# FubarStep_v12.net
KiCad netlist of a schematic drawn in EAGLE
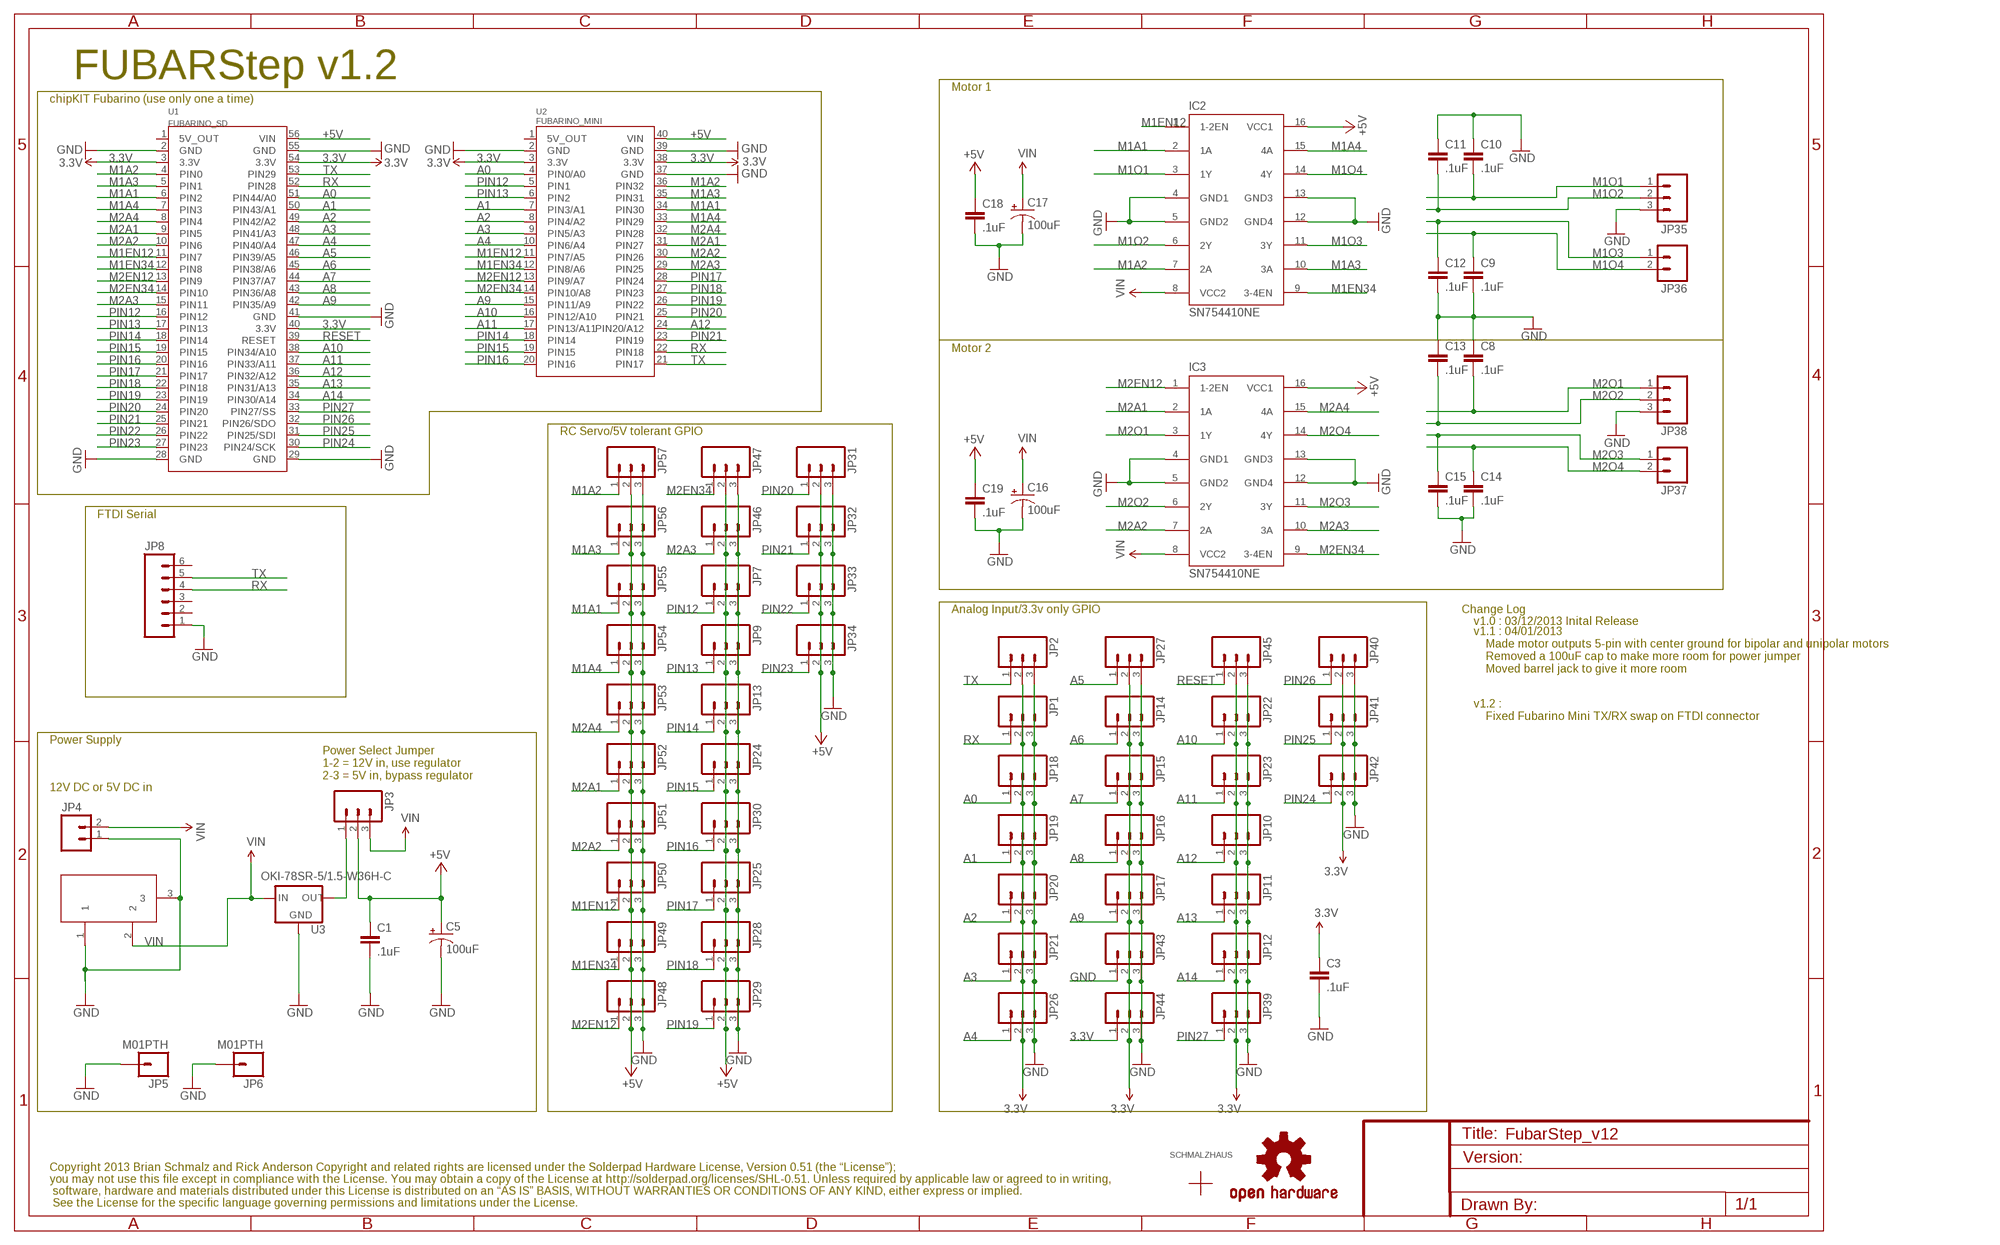
[diagram p0: schematic, sheet 1]

(export (version "E")
  (design (tool "Eeschema 10.0.6"))
  (components
    (comp (ref "C1")
      (value ".1uF")
      (footprint "eagle-import:CAP-PTH-SMALL")
      (libsource (lib "eagle-import") (part "CAPPTH"))
    )
    (comp (ref "C3")
      (value ".1uF")
      (footprint "eagle-import:CAP-PTH-SMALL")
      (libsource (lib "eagle-import") (part "CAPPTH"))
    )
    (comp (ref "C5")
      (value "100uF")
      (footprint "eagle-import:CPOL-RADIAL-100UF-25V")
      (libsource (lib "eagle-import") (part "CAP_POLPTH1"))
    )
    (comp (ref "C8")
      (value ".1uF")
      (footprint "eagle-import:CAP-PTH-SMALL")
      (libsource (lib "eagle-import") (part "CAPPTH"))
    )
    (comp (ref "C9")
      (value ".1uF")
      (footprint "eagle-import:CAP-PTH-SMALL")
      (libsource (lib "eagle-import") (part "CAPPTH"))
    )
    (comp (ref "C10")
      (value ".1uF")
      (footprint "eagle-import:CAP-PTH-SMALL")
      (libsource (lib "eagle-import") (part "CAPPTH"))
    )
    (comp (ref "C11")
      (value ".1uF")
      (footprint "eagle-import:CAP-PTH-SMALL")
      (libsource (lib "eagle-import") (part "CAPPTH"))
    )
    (comp (ref "C12")
      (value ".1uF")
      (footprint "eagle-import:CAP-PTH-SMALL")
      (libsource (lib "eagle-import") (part "CAPPTH"))
    )
    (comp (ref "C13")
      (value ".1uF")
      (footprint "eagle-import:CAP-PTH-SMALL")
      (libsource (lib "eagle-import") (part "CAPPTH"))
    )
    (comp (ref "C14")
      (value ".1uF")
      (footprint "eagle-import:CAP-PTH-SMALL")
      (libsource (lib "eagle-import") (part "CAPPTH"))
    )
    (comp (ref "C15")
      (value ".1uF")
      (footprint "eagle-import:CAP-PTH-SMALL")
      (libsource (lib "eagle-import") (part "CAPPTH"))
    )
    (comp (ref "C16")
      (value "100uF")
      (footprint "eagle-import:CPOL-RADIAL-100UF-25V")
      (libsource (lib "eagle-import") (part "CAP_POLPTH1"))
    )
    (comp (ref "C17")
      (value "100uF")
      (footprint "eagle-import:CPOL-RADIAL-100UF-25V")
      (libsource (lib "eagle-import") (part "CAP_POLPTH1"))
    )
    (comp (ref "C18")
      (value ".1uF")
      (footprint "eagle-import:CAP-PTH-SMALL")
      (libsource (lib "eagle-import") (part "CAPPTH"))
    )
    (comp (ref "C19")
      (value ".1uF")
      (footprint "eagle-import:CAP-PTH-SMALL")
      (libsource (lib "eagle-import") (part "CAPPTH"))
    )
    (comp (ref "IC2")
      (value "SN754410NE")
      (footprint "eagle-import:DIL16")
      (fields (field (name "MF") "Arrow Electronics") (field (name "MPN") "L293E"))
      (libsource (lib "eagle-import") (part "L293E"))
    )
    (comp (ref "IC3")
      (value "SN754410NE")
      (footprint "eagle-import:DIL16")
      (fields (field (name "MF") "Arrow Electronics") (field (name "MPN") "L293E"))
      (libsource (lib "eagle-import") (part "L293E"))
    )
    (comp (ref "JP1")
      (value "M03PTH")
      (footprint "eagle-import:1X03")
      (libsource (lib "eagle-import") (part "M03PTH"))
    )
    (comp (ref "JP2")
      (value "M03PTH")
      (footprint "eagle-import:1X03")
      (libsource (lib "eagle-import") (part "M03PTH"))
    )
    (comp (ref "JP3")
      (value "M03PTH")
      (footprint "eagle-import:1X03")
      (libsource (lib "eagle-import") (part "M03PTH"))
    )
    (comp (ref "JP4")
      (value "M023.5MM")
      (footprint "eagle-import:SCREWTERMINAL-3.5MM-2")
      (libsource (lib "eagle-import") (part "M023.5MM"))
    )
    (comp (ref "JP5")
      (value "M01PTH")
      (footprint "eagle-import:1X01")
      (libsource (lib "eagle-import") (part "M01PTH"))
    )
    (comp (ref "JP6")
      (value "M01PTH")
      (footprint "eagle-import:1X01")
      (libsource (lib "eagle-import") (part "M01PTH"))
    )
    (comp (ref "JP7")
      (value "M03PTH")
      (footprint "eagle-import:1X03")
      (libsource (lib "eagle-import") (part "M03PTH"))
    )
    (comp (ref "JP8")
      (value "M06LOCK")
      (footprint "eagle-import:1X06_LOCK")
      (libsource (lib "eagle-import") (part "M06LOCK"))
    )
    (comp (ref "JP9")
      (value "M03PTH")
      (footprint "eagle-import:1X03")
      (libsource (lib "eagle-import") (part "M03PTH"))
    )
    (comp (ref "JP10")
      (value "M03PTH")
      (footprint "eagle-import:1X03")
      (libsource (lib "eagle-import") (part "M03PTH"))
    )
    (comp (ref "JP11")
      (value "M03PTH")
      (footprint "eagle-import:1X03")
      (libsource (lib "eagle-import") (part "M03PTH"))
    )
    (comp (ref "JP12")
      (value "M03PTH")
      (footprint "eagle-import:1X03")
      (libsource (lib "eagle-import") (part "M03PTH"))
    )
    (comp (ref "JP13")
      (value "M03PTH")
      (footprint "eagle-import:1X03")
      (libsource (lib "eagle-import") (part "M03PTH"))
    )
    (comp (ref "JP14")
      (value "M03PTH")
      (footprint "eagle-import:1X03")
      (libsource (lib "eagle-import") (part "M03PTH"))
    )
    (comp (ref "JP15")
      (value "M03PTH")
      (footprint "eagle-import:1X03")
      (libsource (lib "eagle-import") (part "M03PTH"))
    )
    (comp (ref "JP16")
      (value "M03PTH")
      (footprint "eagle-import:1X03")
      (libsource (lib "eagle-import") (part "M03PTH"))
    )
    (comp (ref "JP17")
      (value "M03PTH")
      (footprint "eagle-import:1X03")
      (libsource (lib "eagle-import") (part "M03PTH"))
    )
    (comp (ref "JP18")
      (value "M03PTH")
      (footprint "eagle-import:1X03")
      (libsource (lib "eagle-import") (part "M03PTH"))
    )
    (comp (ref "JP19")
      (value "M03PTH")
      (footprint "eagle-import:1X03")
      (libsource (lib "eagle-import") (part "M03PTH"))
    )
    (comp (ref "JP20")
      (value "M03PTH")
      (footprint "eagle-import:1X03")
      (libsource (lib "eagle-import") (part "M03PTH"))
    )
    (comp (ref "JP21")
      (value "M03PTH")
      (footprint "eagle-import:1X03")
      (libsource (lib "eagle-import") (part "M03PTH"))
    )
    (comp (ref "JP22")
      (value "M03PTH")
      (footprint "eagle-import:1X03")
      (libsource (lib "eagle-import") (part "M03PTH"))
    )
    (comp (ref "JP23")
      (value "M03PTH")
      (footprint "eagle-import:1X03")
      (libsource (lib "eagle-import") (part "M03PTH"))
    )
    (comp (ref "JP24")
      (value "M03PTH")
      (footprint "eagle-import:1X03")
      (libsource (lib "eagle-import") (part "M03PTH"))
    )
    (comp (ref "JP25")
      (value "M03PTH")
      (footprint "eagle-import:1X03")
      (libsource (lib "eagle-import") (part "M03PTH"))
    )
    (comp (ref "JP26")
      (value "M03PTH")
      (footprint "eagle-import:1X03")
      (libsource (lib "eagle-import") (part "M03PTH"))
    )
    (comp (ref "JP27")
      (value "M03PTH")
      (footprint "eagle-import:1X03")
      (libsource (lib "eagle-import") (part "M03PTH"))
    )
    (comp (ref "JP28")
      (value "M03PTH")
      (footprint "eagle-import:1X03")
      (libsource (lib "eagle-import") (part "M03PTH"))
    )
    (comp (ref "JP29")
      (value "M03PTH")
      (footprint "eagle-import:1X03")
      (libsource (lib "eagle-import") (part "M03PTH"))
    )
    (comp (ref "JP30")
      (value "M03PTH")
      (footprint "eagle-import:1X03")
      (libsource (lib "eagle-import") (part "M03PTH"))
    )
    (comp (ref "JP31")
      (value "M03PTH")
      (footprint "eagle-import:1X03")
      (libsource (lib "eagle-import") (part "M03PTH"))
    )
    (comp (ref "JP32")
      (value "M03PTH")
      (footprint "eagle-import:1X03")
      (libsource (lib "eagle-import") (part "M03PTH"))
    )
    (comp (ref "JP33")
      (value "M03PTH")
      (footprint "eagle-import:1X03")
      (libsource (lib "eagle-import") (part "M03PTH"))
    )
    (comp (ref "JP34")
      (value "M03PTH")
      (footprint "eagle-import:1X03")
      (libsource (lib "eagle-import") (part "M03PTH"))
    )
    (comp (ref "JP35")
      (value "M03SCREW")
      (footprint "eagle-import:SCREWTERMINAL-3.5MM-3")
      (libsource (lib "eagle-import") (part "M03SCREW"))
    )
    (comp (ref "JP36")
      (value "M023.5MM")
      (footprint "eagle-import:SCREWTERMINAL-3.5MM-2")
      (libsource (lib "eagle-import") (part "M023.5MM"))
    )
    (comp (ref "JP37")
      (value "M023.5MM")
      (footprint "eagle-import:SCREWTERMINAL-3.5MM-2")
      (libsource (lib "eagle-import") (part "M023.5MM"))
    )
    (comp (ref "JP38")
      (value "M03SCREW")
      (footprint "eagle-import:SCREWTERMINAL-3.5MM-3")
      (libsource (lib "eagle-import") (part "M03SCREW"))
    )
    (comp (ref "JP39")
      (value "M03PTH")
      (footprint "eagle-import:1X03")
      (libsource (lib "eagle-import") (part "M03PTH"))
    )
    (comp (ref "JP40")
      (value "M03PTH")
      (footprint "eagle-import:1X03")
      (libsource (lib "eagle-import") (part "M03PTH"))
    )
    (comp (ref "JP41")
      (value "M03PTH")
      (footprint "eagle-import:1X03")
      (libsource (lib "eagle-import") (part "M03PTH"))
    )
    (comp (ref "JP42")
      (value "M03PTH")
      (footprint "eagle-import:1X03")
      (libsource (lib "eagle-import") (part "M03PTH"))
    )
    (comp (ref "JP43")
      (value "M03PTH")
      (footprint "eagle-import:1X03")
      (libsource (lib "eagle-import") (part "M03PTH"))
    )
    (comp (ref "JP44")
      (value "M03PTH")
      (footprint "eagle-import:1X03")
      (libsource (lib "eagle-import") (part "M03PTH"))
    )
    (comp (ref "JP45")
      (value "M03PTH")
      (footprint "eagle-import:1X03")
      (libsource (lib "eagle-import") (part "M03PTH"))
    )
    (comp (ref "JP46")
      (value "M03PTH")
      (footprint "eagle-import:1X03")
      (libsource (lib "eagle-import") (part "M03PTH"))
    )
    (comp (ref "JP47")
      (value "M03PTH")
      (footprint "eagle-import:1X03")
      (libsource (lib "eagle-import") (part "M03PTH"))
    )
    (comp (ref "JP48")
      (value "M03PTH")
      (footprint "eagle-import:1X03")
      (libsource (lib "eagle-import") (part "M03PTH"))
    )
    (comp (ref "JP49")
      (value "M03PTH")
      (footprint "eagle-import:1X03")
      (libsource (lib "eagle-import") (part "M03PTH"))
    )
    (comp (ref "JP50")
      (value "M03PTH")
      (footprint "eagle-import:1X03")
      (libsource (lib "eagle-import") (part "M03PTH"))
    )
    (comp (ref "JP51")
      (value "M03PTH")
      (footprint "eagle-import:1X03")
      (libsource (lib "eagle-import") (part "M03PTH"))
    )
    (comp (ref "JP52")
      (value "M03PTH")
      (footprint "eagle-import:1X03")
      (libsource (lib "eagle-import") (part "M03PTH"))
    )
    (comp (ref "JP53")
      (value "M03PTH")
      (footprint "eagle-import:1X03")
      (libsource (lib "eagle-import") (part "M03PTH"))
    )
    (comp (ref "JP54")
      (value "M03PTH")
      (footprint "eagle-import:1X03")
      (libsource (lib "eagle-import") (part "M03PTH"))
    )
    (comp (ref "JP55")
      (value "M03PTH")
      (footprint "eagle-import:1X03")
      (libsource (lib "eagle-import") (part "M03PTH"))
    )
    (comp (ref "JP56")
      (value "M03PTH")
      (footprint "eagle-import:1X03")
      (libsource (lib "eagle-import") (part "M03PTH"))
    )
    (comp (ref "JP57")
      (value "M03PTH")
      (footprint "eagle-import:1X03")
      (libsource (lib "eagle-import") (part "M03PTH"))
    )
    (comp (ref "LOGO1")
      (value "OSHW-LOGOM")
      (footprint "eagle-import:OSHW-LOGO-M")
      (libsource (lib "eagle-import") (part "OSHW-LOGOM"))
    )
    (comp (ref "U$1")
      (value "SCHMALZHAUSSCHMALZHAUS_SMALL")
      (footprint "eagle-import:SCHMALZHAUS_SMALL")
      (libsource (lib "eagle-import") (part "SCHMALZHAUSSCHMALZHAUS_SMALL"))
    )
    (comp (ref "U1")
      (value "FUBARINO_SD")
      (footprint "eagle-import:FUBARINO_SD")
      (libsource (lib "eagle-import") (part "FUBARINO_SD"))
    )
    (comp (ref "U2")
      (value "FUBARINO_MINI")
      (footprint "eagle-import:FUBARINO_MINI")
      (libsource (lib "eagle-import") (part "FUBARINO_MINI"))
    )
    (comp (ref "U3")
      (value "OKI-78SR-5/1.5-W36H-C")
      (footprint "eagle-import:TO220-IGO")
      (libsource (lib "eagle-import") (part "V_REG_78XXSINK"))
    )
    (comp (ref "X1")
      (value "DC21MMX")
      (footprint "eagle-import:DC-21MM")
      (libsource (lib "eagle-import") (part "DC21MMX"))
    )
  )
  (nets
    (net (code "1") (name "+5V") (class "Default")
      (node (ref "C1") (pin "1") (pinfunction "1_1") (pintype "passive"))
      (node (ref "C18") (pin "1") (pinfunction "1_1") (pintype "passive"))
      (node (ref "C19") (pin "1") (pinfunction "1_1") (pintype "passive"))
      (node (ref "C5") (pin "1") (pinfunction "+_1") (pintype "passive"))
      (node (ref "IC2") (pin "16") (pinfunction "VCC1_16") (pintype "power_in"))
      (node (ref "IC3") (pin "16") (pinfunction "VCC1_16") (pintype "power_in"))
      (node (ref "JP13") (pin "2") (pinfunction "2_2") (pintype "passive"))
      (node (ref "JP24") (pin "2") (pinfunction "2_2") (pintype "passive"))
      (node (ref "JP25") (pin "2") (pinfunction "2_2") (pintype "passive"))
      (node (ref "JP28") (pin "2") (pinfunction "2_2") (pintype "passive"))
      (node (ref "JP29") (pin "2") (pinfunction "2_2") (pintype "passive"))
      (node (ref "JP3") (pin "2") (pinfunction "2_2") (pintype "passive"))
      (node (ref "JP30") (pin "2") (pinfunction "2_2") (pintype "passive"))
      (node (ref "JP31") (pin "2") (pinfunction "2_2") (pintype "passive"))
      (node (ref "JP32") (pin "2") (pinfunction "2_2") (pintype "passive"))
      (node (ref "JP33") (pin "2") (pinfunction "2_2") (pintype "passive"))
      (node (ref "JP34") (pin "2") (pinfunction "2_2") (pintype "passive"))
      (node (ref "JP46") (pin "2") (pinfunction "2_2") (pintype "passive"))
      (node (ref "JP47") (pin "2") (pinfunction "2_2") (pintype "passive"))
      (node (ref "JP48") (pin "2") (pinfunction "2_2") (pintype "passive"))
      (node (ref "JP49") (pin "2") (pinfunction "2_2") (pintype "passive"))
      (node (ref "JP50") (pin "2") (pinfunction "2_2") (pintype "passive"))
      (node (ref "JP51") (pin "2") (pinfunction "2_2") (pintype "passive"))
      (node (ref "JP52") (pin "2") (pinfunction "2_2") (pintype "passive"))
      (node (ref "JP53") (pin "2") (pinfunction "2_2") (pintype "passive"))
      (node (ref "JP54") (pin "2") (pinfunction "2_2") (pintype "passive"))
      (node (ref "JP55") (pin "2") (pinfunction "2_2") (pintype "passive"))
      (node (ref "JP56") (pin "2") (pinfunction "2_2") (pintype "passive"))
      (node (ref "JP57") (pin "2") (pinfunction "2_2") (pintype "passive"))
      (node (ref "JP7") (pin "2") (pinfunction "2_2") (pintype "passive"))
      (node (ref "JP9") (pin "2") (pinfunction "2_2") (pintype "passive"))
      (node (ref "U1") (pin "56") (pinfunction "VIN_56") (pintype "bidirectional"))
      (node (ref "U2") (pin "40") (pinfunction "VIN_40") (pintype "bidirectional"))
    )
    (net (code "2") (name "/A0") (class "Default")
      (node (ref "JP18") (pin "1") (pinfunction "1_1") (pintype "passive"))
      (node (ref "U1") (pin "51") (pinfunction "PIN44/A0_51") (pintype "bidirectional"))
      (node (ref "U2") (pin "4") (pinfunction "PIN0/A0_4") (pintype "bidirectional"))
    )
    (net (code "3") (name "/A1") (class "Default")
      (node (ref "JP19") (pin "1") (pinfunction "1_1") (pintype "passive"))
      (node (ref "U1") (pin "50") (pinfunction "PIN43/A1_50") (pintype "bidirectional"))
      (node (ref "U2") (pin "7") (pinfunction "PIN3/A1_7") (pintype "bidirectional"))
    )
    (net (code "4") (name "/A2") (class "Default")
      (node (ref "JP20") (pin "1") (pinfunction "1_1") (pintype "passive"))
      (node (ref "U1") (pin "49") (pinfunction "PIN42/A2_49") (pintype "bidirectional"))
      (node (ref "U2") (pin "8") (pinfunction "PIN4/A2_8") (pintype "bidirectional"))
    )
    (net (code "5") (name "/A3") (class "Default")
      (node (ref "JP21") (pin "1") (pinfunction "1_1") (pintype "passive"))
      (node (ref "U1") (pin "48") (pinfunction "PIN41/A3_48") (pintype "bidirectional"))
      (node (ref "U2") (pin "9") (pinfunction "PIN5/A3_9") (pintype "bidirectional"))
    )
    (net (code "6") (name "/A4") (class "Default")
      (node (ref "JP26") (pin "1") (pinfunction "1_1") (pintype "passive"))
      (node (ref "U1") (pin "47") (pinfunction "PIN40/A4_47") (pintype "bidirectional"))
      (node (ref "U2") (pin "10") (pinfunction "PIN6/A4_10") (pintype "bidirectional"))
    )
    (net (code "7") (name "/A5") (class "Default")
      (node (ref "JP27") (pin "1") (pinfunction "1_1") (pintype "passive"))
      (node (ref "U1") (pin "46") (pinfunction "PIN39/A5_46") (pintype "bidirectional"))
    )
    (net (code "8") (name "/A6") (class "Default")
      (node (ref "JP14") (pin "1") (pinfunction "1_1") (pintype "passive"))
      (node (ref "U1") (pin "45") (pinfunction "PIN38/A6_45") (pintype "bidirectional"))
    )
    (net (code "9") (name "/A7") (class "Default")
      (node (ref "JP15") (pin "1") (pinfunction "1_1") (pintype "passive"))
      (node (ref "U1") (pin "44") (pinfunction "PIN37/A7_44") (pintype "bidirectional"))
    )
    (net (code "10") (name "/A8") (class "Default")
      (node (ref "JP16") (pin "1") (pinfunction "1_1") (pintype "passive"))
      (node (ref "U1") (pin "43") (pinfunction "PIN36/A8_43") (pintype "bidirectional"))
    )
    (net (code "11") (name "/A9") (class "Default")
      (node (ref "JP17") (pin "1") (pinfunction "1_1") (pintype "passive"))
      (node (ref "U1") (pin "42") (pinfunction "PIN35/A9_42") (pintype "bidirectional"))
      (node (ref "U2") (pin "15") (pinfunction "PIN11/A9_15") (pintype "bidirectional"))
    )
    (net (code "12") (name "/A10") (class "Default")
      (node (ref "JP22") (pin "1") (pinfunction "1_1") (pintype "passive"))
      (node (ref "U1") (pin "38") (pinfunction "PIN34/A10_38") (pintype "bidirectional"))
      (node (ref "U2") (pin "16") (pinfunction "PIN12/A10_16") (pintype "bidirectional"))
    )
    (net (code "13") (name "/A11") (class "Default")
      (node (ref "JP23") (pin "1") (pinfunction "1_1") (pintype "passive"))
      (node (ref "U1") (pin "37") (pinfunction "PIN33/A11_37") (pintype "bidirectional"))
      (node (ref "U2") (pin "17") (pinfunction "PIN13/A11_17") (pintype "bidirectional"))
    )
    (net (code "14") (name "/A12") (class "Default")
      (node (ref "JP10") (pin "1") (pinfunction "1_1") (pintype "passive"))
      (node (ref "U1") (pin "36") (pinfunction "PIN32/A12_36") (pintype "bidirectional"))
      (node (ref "U2") (pin "24") (pinfunction "PIN20/A12_24") (pintype "bidirectional"))
    )
    (net (code "15") (name "/A13") (class "Default")
      (node (ref "JP11") (pin "1") (pinfunction "1_1") (pintype "passive"))
      (node (ref "U1") (pin "35") (pinfunction "PIN31/A13_35") (pintype "bidirectional"))
    )
    (net (code "16") (name "/A14") (class "Default")
      (node (ref "JP12") (pin "1") (pinfunction "1_1") (pintype "passive"))
      (node (ref "U1") (pin "34") (pinfunction "PIN30/A14_34") (pintype "bidirectional"))
    )
    (net (code "17") (name "/M1A1") (class "Default")
      (node (ref "IC2") (pin "2") (pinfunction "1A_2") (pintype "input"))
      (node (ref "JP55") (pin "1") (pinfunction "1_1") (pintype "passive"))
      (node (ref "U1") (pin "6") (pinfunction "PIN2_6") (pintype "bidirectional"))
      (node (ref "U2") (pin "34") (pinfunction "PIN30_34") (pintype "bidirectional"))
    )
    (net (code "18") (name "/M1A2") (class "Default")
      (node (ref "IC2") (pin "7") (pinfunction "2A_7") (pintype "input"))
      (node (ref "JP57") (pin "1") (pinfunction "1_1") (pintype "passive"))
      (node (ref "U1") (pin "4") (pinfunction "PIN0_4") (pintype "bidirectional"))
      (node (ref "U2") (pin "36") (pinfunction "PIN32_36") (pintype "bidirectional"))
    )
    (net (code "19") (name "/M1A3") (class "Default")
      (node (ref "IC2") (pin "10") (pinfunction "3A_10") (pintype "input"))
      (node (ref "JP56") (pin "1") (pinfunction "1_1") (pintype "passive"))
      (node (ref "U1") (pin "5") (pinfunction "PIN1_5") (pintype "bidirectional"))
      (node (ref "U2") (pin "35") (pinfunction "PIN31_35") (pintype "bidirectional"))
    )
    (net (code "20") (name "/M1A4") (class "Default")
      (node (ref "IC2") (pin "15") (pinfunction "4A_15") (pintype "input"))
      (node (ref "JP54") (pin "1") (pinfunction "1_1") (pintype "passive"))
      (node (ref "U1") (pin "7") (pinfunction "PIN3_7") (pintype "bidirectional"))
      (node (ref "U2") (pin "33") (pinfunction "PIN29_33") (pintype "bidirectional"))
    )
    (net (code "21") (name "/M1EN12") (class "Default")
      (node (ref "IC2") (pin "1") (pinfunction "1-2EN_1") (pintype "input"))
      (node (ref "JP50") (pin "1") (pinfunction "1_1") (pintype "passive"))
      (node (ref "U1") (pin "11") (pinfunction "PIN7_11") (pintype "bidirectional"))
      (node (ref "U2") (pin "11") (pinfunction "PIN7/A5_11") (pintype "bidirectional"))
    )
    (net (code "22") (name "/M1EN34") (class "Default")
      (node (ref "IC2") (pin "9") (pinfunction "3-4EN_9") (pintype "input"))
      (node (ref "JP49") (pin "1") (pinfunction "1_1") (pintype "passive"))
      (node (ref "U1") (pin "12") (pinfunction "PIN8_12") (pintype "bidirectional"))
      (node (ref "U2") (pin "12") (pinfunction "PIN8/A6_12") (pintype "bidirectional"))
    )
    (net (code "23") (name "/M1O1") (class "Default")
      (node (ref "C10") (pin "2") (pinfunction "2_2") (pintype "passive"))
      (node (ref "IC2") (pin "3") (pinfunction "1Y_3") (pintype "output"))
      (node (ref "JP35") (pin "1") (pinfunction "1_1") (pintype "passive"))
    )
    (net (code "24") (name "/M1O2") (class "Default")
      (node (ref "C11") (pin "2") (pinfunction "2_2") (pintype "passive"))
      (node (ref "IC2") (pin "6") (pinfunction "2Y_6") (pintype "output"))
      (node (ref "JP35") (pin "2") (pinfunction "2_2") (pintype "passive"))
    )
    (net (code "25") (name "/M1O3") (class "Default")
      (node (ref "C12") (pin "1") (pinfunction "1_1") (pintype "passive"))
      (node (ref "IC2") (pin "11") (pinfunction "3Y_11") (pintype "output"))
      (node (ref "JP36") (pin "1") (pinfunction "1_1") (pintype "passive"))
    )
    (net (code "26") (name "/M1O4") (class "Default")
      (node (ref "C9") (pin "1") (pinfunction "1_1") (pintype "passive"))
      (node (ref "IC2") (pin "14") (pinfunction "4Y_14") (pintype "output"))
      (node (ref "JP36") (pin "2") (pinfunction "2_2") (pintype "passive"))
    )
    (net (code "27") (name "/M2A1") (class "Default")
      (node (ref "IC3") (pin "2") (pinfunction "1A_2") (pintype "input"))
      (node (ref "JP52") (pin "1") (pinfunction "1_1") (pintype "passive"))
      (node (ref "U1") (pin "9") (pinfunction "PIN5_9") (pintype "bidirectional"))
      (node (ref "U2") (pin "31") (pinfunction "PIN27_31") (pintype "bidirectional"))
    )
    (net (code "28") (name "/M2A2") (class "Default")
      (node (ref "IC3") (pin "7") (pinfunction "2A_7") (pintype "input"))
      (node (ref "JP51") (pin "1") (pinfunction "1_1") (pintype "passive"))
      (node (ref "U1") (pin "10") (pinfunction "PIN6_10") (pintype "bidirectional"))
      (node (ref "U2") (pin "30") (pinfunction "PIN26_30") (pintype "bidirectional"))
    )
    (net (code "29") (name "/M2A3") (class "Default")
      (node (ref "IC3") (pin "10") (pinfunction "3A_10") (pintype "input"))
      (node (ref "JP46") (pin "1") (pinfunction "1_1") (pintype "passive"))
      (node (ref "U1") (pin "15") (pinfunction "PIN11_15") (pintype "bidirectional"))
      (node (ref "U2") (pin "29") (pinfunction "PIN25_29") (pintype "bidirectional"))
    )
    (net (code "30") (name "/M2A4") (class "Default")
      (node (ref "IC3") (pin "15") (pinfunction "4A_15") (pintype "input"))
      (node (ref "JP53") (pin "1") (pinfunction "1_1") (pintype "passive"))
      (node (ref "U1") (pin "8") (pinfunction "PIN4_8") (pintype "bidirectional"))
      (node (ref "U2") (pin "32") (pinfunction "PIN28_32") (pintype "bidirectional"))
    )
    (net (code "31") (name "/M2EN12") (class "Default")
      (node (ref "IC3") (pin "1") (pinfunction "1-2EN_1") (pintype "input"))
      (node (ref "JP48") (pin "1") (pinfunction "1_1") (pintype "passive"))
      (node (ref "U1") (pin "13") (pinfunction "PIN9_13") (pintype "bidirectional"))
      (node (ref "U2") (pin "13") (pinfunction "PIN9/A7_13") (pintype "bidirectional"))
    )
    (net (code "32") (name "/M2EN34") (class "Default")
      (node (ref "IC3") (pin "9") (pinfunction "3-4EN_9") (pintype "input"))
      (node (ref "JP47") (pin "1") (pinfunction "1_1") (pintype "passive"))
      (node (ref "U1") (pin "14") (pinfunction "PIN10_14") (pintype "bidirectional"))
      (node (ref "U2") (pin "14") (pinfunction "PIN10/A8_14") (pintype "bidirectional"))
    )
    (net (code "33") (name "/M2O1") (class "Default")
      (node (ref "C8") (pin "2") (pinfunction "2_2") (pintype "passive"))
      (node (ref "IC3") (pin "3") (pinfunction "1Y_3") (pintype "output"))
      (node (ref "JP38") (pin "1") (pinfunction "1_1") (pintype "passive"))
    )
    (net (code "34") (name "/M2O2") (class "Default")
      (node (ref "C13") (pin "2") (pinfunction "2_2") (pintype "passive"))
      (node (ref "IC3") (pin "6") (pinfunction "2Y_6") (pintype "output"))
      (node (ref "JP38") (pin "2") (pinfunction "2_2") (pintype "passive"))
    )
    (net (code "35") (name "/M2O3") (class "Default")
      (node (ref "C15") (pin "1") (pinfunction "1_1") (pintype "passive"))
      (node (ref "IC3") (pin "11") (pinfunction "3Y_11") (pintype "output"))
      (node (ref "JP37") (pin "1") (pinfunction "1_1") (pintype "passive"))
    )
    (net (code "36") (name "/M2O4") (class "Default")
      (node (ref "C14") (pin "1") (pinfunction "1_1") (pintype "passive"))
      (node (ref "IC3") (pin "14") (pinfunction "4Y_14") (pintype "output"))
      (node (ref "JP37") (pin "2") (pinfunction "2_2") (pintype "passive"))
    )
    (net (code "37") (name "/PIN12") (class "Default")
      (node (ref "JP7") (pin "1") (pinfunction "1_1") (pintype "passive"))
      (node (ref "U1") (pin "16") (pinfunction "PIN12_16") (pintype "bidirectional"))
      (node (ref "U2") (pin "5") (pinfunction "PIN1_5") (pintype "bidirectional"))
    )
    (net (code "38") (name "/PIN13") (class "Default")
      (node (ref "JP9") (pin "1") (pinfunction "1_1") (pintype "passive"))
      (node (ref "U1") (pin "17") (pinfunction "PIN13_17") (pintype "bidirectional"))
      (node (ref "U2") (pin "6") (pinfunction "PIN2_6") (pintype "bidirectional"))
    )
    (net (code "39") (name "/PIN14") (class "Default")
      (node (ref "JP13") (pin "1") (pinfunction "1_1") (pintype "passive"))
      (node (ref "U1") (pin "18") (pinfunction "PIN14_18") (pintype "bidirectional"))
      (node (ref "U2") (pin "18") (pinfunction "PIN14_18") (pintype "bidirectional"))
    )
    (net (code "40") (name "/PIN15") (class "Default")
      (node (ref "JP24") (pin "1") (pinfunction "1_1") (pintype "passive"))
      (node (ref "U1") (pin "19") (pinfunction "PIN15_19") (pintype "bidirectional"))
      (node (ref "U2") (pin "19") (pinfunction "PIN15_19") (pintype "bidirectional"))
    )
    (net (code "41") (name "/PIN16") (class "Default")
      (node (ref "JP30") (pin "1") (pinfunction "1_1") (pintype "passive"))
      (node (ref "U1") (pin "20") (pinfunction "PIN16_20") (pintype "bidirectional"))
      (node (ref "U2") (pin "20") (pinfunction "PIN16_20") (pintype "bidirectional"))
    )
    (net (code "42") (name "/PIN17") (class "Default")
      (node (ref "JP25") (pin "1") (pinfunction "1_1") (pintype "passive"))
      (node (ref "U1") (pin "21") (pinfunction "PIN17_21") (pintype "bidirectional"))
      (node (ref "U2") (pin "28") (pinfunction "PIN24_28") (pintype "bidirectional"))
    )
    (net (code "43") (name "/PIN18") (class "Default")
      (node (ref "JP28") (pin "1") (pinfunction "1_1") (pintype "passive"))
      (node (ref "U1") (pin "22") (pinfunction "PIN18_22") (pintype "bidirectional"))
      (node (ref "U2") (pin "27") (pinfunction "PIN23_27") (pintype "bidirectional"))
    )
    (net (code "44") (name "/PIN19") (class "Default")
      (node (ref "JP29") (pin "1") (pinfunction "1_1") (pintype "passive"))
      (node (ref "U1") (pin "23") (pinfunction "PIN19_23") (pintype "bidirectional"))
      (node (ref "U2") (pin "26") (pinfunction "PIN22_26") (pintype "bidirectional"))
    )
    (net (code "45") (name "/PIN20") (class "Default")
      (node (ref "JP31") (pin "1") (pinfunction "1_1") (pintype "passive"))
      (node (ref "U1") (pin "24") (pinfunction "PIN20_24") (pintype "bidirectional"))
      (node (ref "U2") (pin "25") (pinfunction "PIN21_25") (pintype "bidirectional"))
    )
    (net (code "46") (name "/PIN21") (class "Default")
      (node (ref "JP32") (pin "1") (pinfunction "1_1") (pintype "passive"))
      (node (ref "U1") (pin "25") (pinfunction "PIN21_25") (pintype "bidirectional"))
      (node (ref "U2") (pin "23") (pinfunction "PIN19_23") (pintype "bidirectional"))
    )
    (net (code "47") (name "/PIN22") (class "Default")
      (node (ref "JP33") (pin "1") (pinfunction "1_1") (pintype "passive"))
      (node (ref "U1") (pin "26") (pinfunction "PIN22_26") (pintype "bidirectional"))
    )
    (net (code "48") (name "/PIN23") (class "Default")
      (node (ref "JP34") (pin "1") (pinfunction "1_1") (pintype "passive"))
      (node (ref "U1") (pin "27") (pinfunction "PIN23_27") (pintype "bidirectional"))
    )
    (net (code "49") (name "/PIN24") (class "Default")
      (node (ref "JP42") (pin "1") (pinfunction "1_1") (pintype "passive"))
      (node (ref "U1") (pin "30") (pinfunction "PIN24/SCK_30") (pintype "bidirectional"))
    )
    (net (code "50") (name "/PIN25") (class "Default")
      (node (ref "JP41") (pin "1") (pinfunction "1_1") (pintype "passive"))
      (node (ref "U1") (pin "31") (pinfunction "PIN25/SDI_31") (pintype "bidirectional"))
    )
    (net (code "51") (name "/PIN26") (class "Default")
      (node (ref "JP40") (pin "1") (pinfunction "1_1") (pintype "passive"))
      (node (ref "U1") (pin "32") (pinfunction "PIN26/SDO_32") (pintype "bidirectional"))
    )
    (net (code "52") (name "/PIN27") (class "Default")
      (node (ref "JP39") (pin "1") (pinfunction "1_1") (pintype "passive"))
      (node (ref "U1") (pin "33") (pinfunction "PIN27/SS_33") (pintype "bidirectional"))
    )
    (net (code "53") (name "/RESET") (class "Default")
      (node (ref "JP45") (pin "1") (pinfunction "1_1") (pintype "passive"))
      (node (ref "U1") (pin "39") (pinfunction "RESET_39") (pintype "bidirectional"))
    )
    (net (code "54") (name "/RX") (class "Default")
      (node (ref "JP1") (pin "1") (pinfunction "1_1") (pintype "passive"))
      (node (ref "JP8") (pin "4") (pinfunction "4_4") (pintype "passive"))
      (node (ref "U1") (pin "52") (pinfunction "PIN28_52") (pintype "bidirectional"))
      (node (ref "U2") (pin "22") (pinfunction "PIN18_22") (pintype "bidirectional"))
    )
    (net (code "55") (name "/TX") (class "Default")
      (node (ref "JP2") (pin "1") (pinfunction "1_1") (pintype "passive"))
      (node (ref "JP8") (pin "5") (pinfunction "5_5") (pintype "passive"))
      (node (ref "U1") (pin "53") (pinfunction "PIN29_53") (pintype "bidirectional"))
      (node (ref "U2") (pin "21") (pinfunction "PIN17_21") (pintype "bidirectional"))
    )
    (net (code "56") (name "3.3V") (class "Default")
      (node (ref "C3") (pin "1") (pinfunction "1_1") (pintype "passive"))
      (node (ref "JP1") (pin "2") (pinfunction "2_2") (pintype "passive"))
      (node (ref "JP10") (pin "2") (pinfunction "2_2") (pintype "passive"))
      (node (ref "JP11") (pin "2") (pinfunction "2_2") (pintype "passive"))
      (node (ref "JP12") (pin "2") (pinfunction "2_2") (pintype "passive"))
      (node (ref "JP14") (pin "2") (pinfunction "2_2") (pintype "passive"))
      (node (ref "JP15") (pin "2") (pinfunction "2_2") (pintype "passive"))
      (node (ref "JP16") (pin "2") (pinfunction "2_2") (pintype "passive"))
      (node (ref "JP17") (pin "2") (pinfunction "2_2") (pintype "passive"))
      (node (ref "JP18") (pin "2") (pinfunction "2_2") (pintype "passive"))
      (node (ref "JP19") (pin "2") (pinfunction "2_2") (pintype "passive"))
      (node (ref "JP2") (pin "2") (pinfunction "2_2") (pintype "passive"))
      (node (ref "JP20") (pin "2") (pinfunction "2_2") (pintype "passive"))
      (node (ref "JP21") (pin "2") (pinfunction "2_2") (pintype "passive"))
      (node (ref "JP22") (pin "2") (pinfunction "2_2") (pintype "passive"))
      (node (ref "JP23") (pin "2") (pinfunction "2_2") (pintype "passive"))
      (node (ref "JP26") (pin "2") (pinfunction "2_2") (pintype "passive"))
      (node (ref "JP27") (pin "2") (pinfunction "2_2") (pintype "passive"))
      (node (ref "JP39") (pin "2") (pinfunction "2_2") (pintype "passive"))
      (node (ref "JP40") (pin "2") (pinfunction "2_2") (pintype "passive"))
      (node (ref "JP41") (pin "2") (pinfunction "2_2") (pintype "passive"))
      (node (ref "JP42") (pin "2") (pinfunction "2_2") (pintype "passive"))
      (node (ref "JP43") (pin "2") (pinfunction "2_2") (pintype "passive"))
      (node (ref "JP44") (pin "1") (pinfunction "1_1") (pintype "passive"))
      (node (ref "JP44") (pin "2") (pinfunction "2_2") (pintype "passive"))
      (node (ref "JP45") (pin "2") (pinfunction "2_2") (pintype "passive"))
      (node (ref "U1") (pin "3") (pinfunction "3.3V_3") (pintype "bidirectional"))
      (node (ref "U1") (pin "40") (pinfunction "3.3V_40") (pintype "bidirectional"))
      (node (ref "U1") (pin "54") (pinfunction "3.3V_54") (pintype "bidirectional"))
      (node (ref "U2") (pin "3") (pinfunction "3.3V_3") (pintype "bidirectional"))
      (node (ref "U2") (pin "38") (pinfunction "3.3V_38") (pintype "bidirectional"))
    )
    (net (code "57") (name "GND") (class "Default")
      (node (ref "C1") (pin "2") (pinfunction "2_2") (pintype "passive"))
      (node (ref "C10") (pin "1") (pinfunction "1_1") (pintype "passive"))
      (node (ref "C11") (pin "1") (pinfunction "1_1") (pintype "passive"))
      (node (ref "C12") (pin "2") (pinfunction "2_2") (pintype "passive"))
      (node (ref "C13") (pin "1") (pinfunction "1_1") (pintype "passive"))
      (node (ref "C14") (pin "2") (pinfunction "2_2") (pintype "passive"))
      (node (ref "C15") (pin "2") (pinfunction "2_2") (pintype "passive"))
      (node (ref "C16") (pin "2") (pinfunction "-_2") (pintype "passive"))
      (node (ref "C17") (pin "2") (pinfunction "-_2") (pintype "passive"))
      (node (ref "C18") (pin "2") (pinfunction "2_2") (pintype "passive"))
      (node (ref "C19") (pin "2") (pinfunction "2_2") (pintype "passive"))
      (node (ref "C3") (pin "2") (pinfunction "2_2") (pintype "passive"))
      (node (ref "C5") (pin "2") (pinfunction "-_2") (pintype "passive"))
      (node (ref "C8") (pin "1") (pinfunction "1_1") (pintype "passive"))
      (node (ref "C9") (pin "2") (pinfunction "2_2") (pintype "passive"))
      (node (ref "IC2") (pin "12") (pinfunction "GND4_12") (pintype "power_in"))
      (node (ref "IC2") (pin "13") (pinfunction "GND3_13") (pintype "power_in"))
      (node (ref "IC2") (pin "4") (pinfunction "GND1_4") (pintype "power_in"))
      (node (ref "IC2") (pin "5") (pinfunction "GND2_5") (pintype "power_in"))
      (node (ref "IC3") (pin "12") (pinfunction "GND4_12") (pintype "power_in"))
      (node (ref "IC3") (pin "13") (pinfunction "GND3_13") (pintype "power_in"))
      (node (ref "IC3") (pin "4") (pinfunction "GND1_4") (pintype "power_in"))
      (node (ref "IC3") (pin "5") (pinfunction "GND2_5") (pintype "power_in"))
      (node (ref "JP1") (pin "3") (pinfunction "3_3") (pintype "passive"))
      (node (ref "JP10") (pin "3") (pinfunction "3_3") (pintype "passive"))
      (node (ref "JP11") (pin "3") (pinfunction "3_3") (pintype "passive"))
      (node (ref "JP12") (pin "3") (pinfunction "3_3") (pintype "passive"))
      (node (ref "JP13") (pin "3") (pinfunction "3_3") (pintype "passive"))
      (node (ref "JP14") (pin "3") (pinfunction "3_3") (pintype "passive"))
      (node (ref "JP15") (pin "3") (pinfunction "3_3") (pintype "passive"))
      (node (ref "JP16") (pin "3") (pinfunction "3_3") (pintype "passive"))
      (node (ref "JP17") (pin "3") (pinfunction "3_3") (pintype "passive"))
      (node (ref "JP18") (pin "3") (pinfunction "3_3") (pintype "passive"))
      (node (ref "JP19") (pin "3") (pinfunction "3_3") (pintype "passive"))
      (node (ref "JP2") (pin "3") (pinfunction "3_3") (pintype "passive"))
      (node (ref "JP20") (pin "3") (pinfunction "3_3") (pintype "passive"))
      (node (ref "JP21") (pin "3") (pinfunction "3_3") (pintype "passive"))
      (node (ref "JP22") (pin "3") (pinfunction "3_3") (pintype "passive"))
      (node (ref "JP23") (pin "3") (pinfunction "3_3") (pintype "passive"))
      (node (ref "JP24") (pin "3") (pinfunction "3_3") (pintype "passive"))
      (node (ref "JP25") (pin "3") (pinfunction "3_3") (pintype "passive"))
      (node (ref "JP26") (pin "3") (pinfunction "3_3") (pintype "passive"))
      (node (ref "JP27") (pin "3") (pinfunction "3_3") (pintype "passive"))
      (node (ref "JP28") (pin "3") (pinfunction "3_3") (pintype "passive"))
      (node (ref "JP29") (pin "3") (pinfunction "3_3") (pintype "passive"))
      (node (ref "JP30") (pin "3") (pinfunction "3_3") (pintype "passive"))
      (node (ref "JP31") (pin "3") (pinfunction "3_3") (pintype "passive"))
      (node (ref "JP32") (pin "3") (pinfunction "3_3") (pintype "passive"))
      (node (ref "JP33") (pin "3") (pinfunction "3_3") (pintype "passive"))
      (node (ref "JP34") (pin "3") (pinfunction "3_3") (pintype "passive"))
      (node (ref "JP35") (pin "3") (pinfunction "3_3") (pintype "passive"))
      (node (ref "JP38") (pin "3") (pinfunction "3_3") (pintype "passive"))
      (node (ref "JP39") (pin "3") (pinfunction "3_3") (pintype "passive"))
      (node (ref "JP4") (pin "1") (pinfunction "1_1") (pintype "passive"))
      (node (ref "JP40") (pin "3") (pinfunction "3_3") (pintype "passive"))
      (node (ref "JP41") (pin "3") (pinfunction "3_3") (pintype "passive"))
      (node (ref "JP42") (pin "3") (pinfunction "3_3") (pintype "passive"))
      (node (ref "JP43") (pin "1") (pinfunction "1_1") (pintype "passive"))
      (node (ref "JP43") (pin "3") (pinfunction "3_3") (pintype "passive"))
      (node (ref "JP44") (pin "3") (pinfunction "3_3") (pintype "passive"))
      (node (ref "JP45") (pin "3") (pinfunction "3_3") (pintype "passive"))
      (node (ref "JP46") (pin "3") (pinfunction "3_3") (pintype "passive"))
      (node (ref "JP47") (pin "3") (pinfunction "3_3") (pintype "passive"))
      (node (ref "JP48") (pin "3") (pinfunction "3_3") (pintype "passive"))
      (node (ref "JP49") (pin "3") (pinfunction "3_3") (pintype "passive"))
      (node (ref "JP5") (pin "1") (pinfunction "1_1") (pintype "passive"))
      (node (ref "JP50") (pin "3") (pinfunction "3_3") (pintype "passive"))
      (node (ref "JP51") (pin "3") (pinfunction "3_3") (pintype "passive"))
      (node (ref "JP52") (pin "3") (pinfunction "3_3") (pintype "passive"))
      (node (ref "JP53") (pin "3") (pinfunction "3_3") (pintype "passive"))
      (node (ref "JP54") (pin "3") (pinfunction "3_3") (pintype "passive"))
      (node (ref "JP55") (pin "3") (pinfunction "3_3") (pintype "passive"))
      (node (ref "JP56") (pin "3") (pinfunction "3_3") (pintype "passive"))
      (node (ref "JP57") (pin "3") (pinfunction "3_3") (pintype "passive"))
      (node (ref "JP6") (pin "1") (pinfunction "1_1") (pintype "passive"))
      (node (ref "JP7") (pin "3") (pinfunction "3_3") (pintype "passive"))
      (node (ref "JP8") (pin "1") (pinfunction "1_1") (pintype "passive"))
      (node (ref "JP9") (pin "3") (pinfunction "3_3") (pintype "passive"))
      (node (ref "U1") (pin "2") (pinfunction "GND_2") (pintype "bidirectional"))
      (node (ref "U1") (pin "28") (pinfunction "GND_28") (pintype "bidirectional"))
      (node (ref "U1") (pin "29") (pinfunction "GND_29") (pintype "bidirectional"))
      (node (ref "U1") (pin "41") (pinfunction "GND_41") (pintype "bidirectional"))
      (node (ref "U1") (pin "55") (pinfunction "GND_55") (pintype "bidirectional"))
      (node (ref "U2") (pin "2") (pinfunction "GND_2") (pintype "bidirectional"))
      (node (ref "U2") (pin "37") (pinfunction "GND_37") (pintype "bidirectional"))
      (node (ref "U2") (pin "39") (pinfunction "GND_39") (pintype "bidirectional"))
      (node (ref "U3") (pin "GND") (pinfunction "GND_GND") (pintype "input"))
      (node (ref "X1") (pin "1") (pinfunction "1_1") (pintype "power_in"))
      (node (ref "X1") (pin "3") (pinfunction "3_3") (pintype "power_in"))
    )
    (net (code "58") (name "Net-(JP3-Pad1)") (class "Default")
      (node (ref "JP3") (pin "1") (pinfunction "1_1") (pintype "passive"))
      (node (ref "U3") (pin "OUT") (pinfunction "OUT_OUT") (pintype "output"))
    )
    (net (code "59") (name "VIN") (class "Default")
      (node (ref "C16") (pin "1") (pinfunction "+_1") (pintype "passive"))
      (node (ref "C17") (pin "1") (pinfunction "+_1") (pintype "passive"))
      (node (ref "IC2") (pin "8") (pinfunction "VCC2_8") (pintype "power_in"))
      (node (ref "IC3") (pin "8") (pinfunction "VCC2_8") (pintype "power_in"))
      (node (ref "JP3") (pin "3") (pinfunction "3_3") (pintype "passive"))
      (node (ref "JP4") (pin "2") (pinfunction "2_2") (pintype "passive"))
      (node (ref "U3") (pin "IN") (pinfunction "IN_IN") (pintype "input"))
      (node (ref "X1") (pin "2") (pinfunction "2_2") (pintype "power_in"))
    )
    (net (code "60") (name "unconnected-(JP8-Pad2)") (class "Default")
      (node (ref "JP8") (pin "2") (pinfunction "2_2") (pintype "passive"))
    )
    (net (code "61") (name "unconnected-(JP8-Pad3)") (class "Default")
      (node (ref "JP8") (pin "3") (pinfunction "3_3") (pintype "passive"))
    )
    (net (code "62") (name "unconnected-(JP8-Pad6)") (class "Default")
      (node (ref "JP8") (pin "6") (pinfunction "6_6") (pintype "passive"))
    )
    (net (code "63") (name "unconnected-(U1-5V_OUT-Pad1)") (class "Default")
      (node (ref "U1") (pin "1") (pinfunction "5V_OUT_1") (pintype "bidirectional"))
    )
    (net (code "64") (name "unconnected-(U2-5V_OUT-Pad1)") (class "Default")
      (node (ref "U2") (pin "1") (pinfunction "5V_OUT_1") (pintype "bidirectional"))
    )
  )
)
